# 3P4W_v1p0.net
KiCad netlist of a schematic drawn in EAGLE
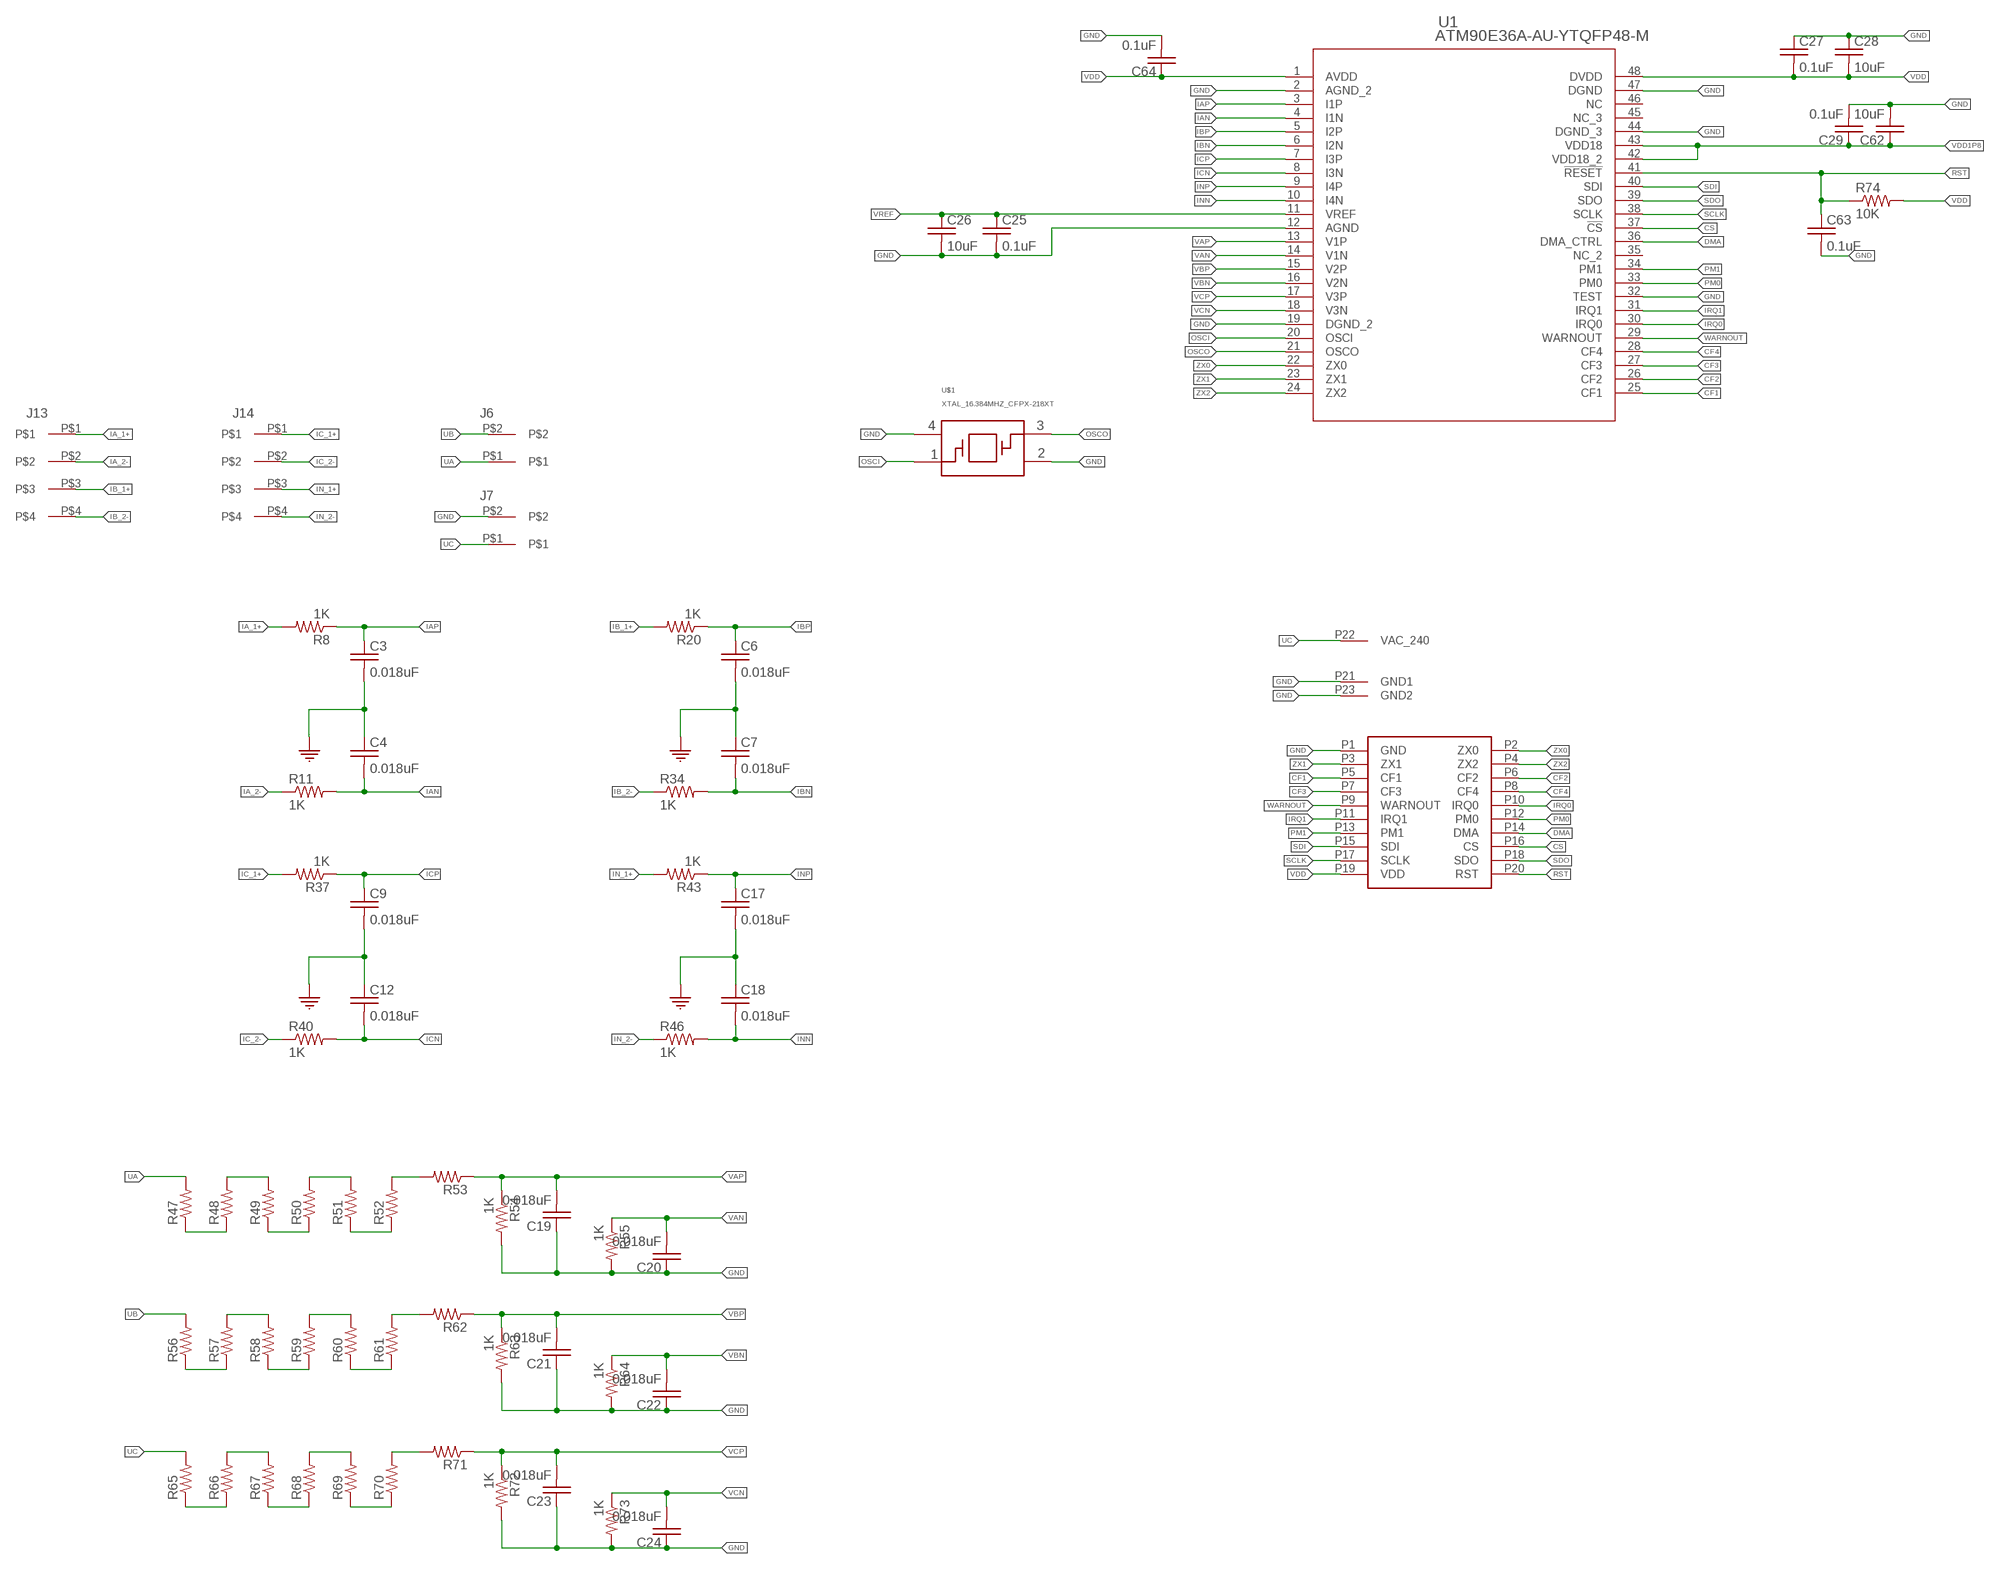
[diagram p0: schematic, sheet 1]

(export (version "E")
  (design (tool "Eeschema 10.0.6"))
  (components
    (comp (ref "C3")
      (value "0.018uF")
      (footprint "eagle-import:0402")
      (libsource (lib "eagle-import") (part "C_0402"))
    )
    (comp (ref "C4")
      (value "0.018uF")
      (footprint "eagle-import:0402")
      (libsource (lib "eagle-import") (part "C_0402"))
    )
    (comp (ref "C6")
      (value "0.018uF")
      (footprint "eagle-import:0402")
      (libsource (lib "eagle-import") (part "C_0402"))
    )
    (comp (ref "C7")
      (value "0.018uF")
      (footprint "eagle-import:0402")
      (libsource (lib "eagle-import") (part "C_0402"))
    )
    (comp (ref "C9")
      (value "0.018uF")
      (footprint "eagle-import:0402")
      (libsource (lib "eagle-import") (part "C_0402"))
    )
    (comp (ref "C12")
      (value "0.018uF")
      (footprint "eagle-import:0402")
      (libsource (lib "eagle-import") (part "C_0402"))
    )
    (comp (ref "C17")
      (value "0.018uF")
      (footprint "eagle-import:0402")
      (libsource (lib "eagle-import") (part "C_0402"))
    )
    (comp (ref "C18")
      (value "0.018uF")
      (footprint "eagle-import:0402")
      (libsource (lib "eagle-import") (part "C_0402"))
    )
    (comp (ref "C19")
      (value "0.018uF")
      (footprint "eagle-import:0402")
      (libsource (lib "eagle-import") (part "C_0402"))
    )
    (comp (ref "C20")
      (value "0.018uF")
      (footprint "eagle-import:0402")
      (libsource (lib "eagle-import") (part "C_0402"))
    )
    (comp (ref "C21")
      (value "0.018uF")
      (footprint "eagle-import:0402")
      (libsource (lib "eagle-import") (part "C_0402"))
    )
    (comp (ref "C22")
      (value "0.018uF")
      (footprint "eagle-import:0402")
      (libsource (lib "eagle-import") (part "C_0402"))
    )
    (comp (ref "C23")
      (value "0.018uF")
      (footprint "eagle-import:0402")
      (libsource (lib "eagle-import") (part "C_0402"))
    )
    (comp (ref "C24")
      (value "0.018uF")
      (footprint "eagle-import:0402")
      (libsource (lib "eagle-import") (part "C_0402"))
    )
    (comp (ref "C25")
      (value "0.1uF")
      (footprint "eagle-import:0402")
      (libsource (lib "eagle-import") (part "C_0402"))
    )
    (comp (ref "C26")
      (value "10uF")
      (footprint "eagle-import:0402")
      (libsource (lib "eagle-import") (part "C_0402"))
    )
    (comp (ref "C27")
      (value "0.1uF")
      (footprint "eagle-import:0402")
      (libsource (lib "eagle-import") (part "C_0402"))
    )
    (comp (ref "C28")
      (value "10uF")
      (footprint "eagle-import:0402")
      (libsource (lib "eagle-import") (part "C_0402"))
    )
    (comp (ref "C29")
      (value "0.1uF")
      (footprint "eagle-import:0402")
      (libsource (lib "eagle-import") (part "C_0402"))
    )
    (comp (ref "C62")
      (value "10uF")
      (footprint "eagle-import:0402")
      (libsource (lib "eagle-import") (part "C_0402"))
    )
    (comp (ref "C63")
      (value "0.1uF")
      (footprint "eagle-import:0402")
      (libsource (lib "eagle-import") (part "C_0402"))
    )
    (comp (ref "C64")
      (value "0.1uF")
      (footprint "eagle-import:0402")
      (libsource (lib "eagle-import") (part "C_0402"))
    )
    (comp (ref "J6")
      (value "3.81MM_1_X_2_RT_ANGLE_PLUG_HEADER")
      (footprint "eagle-import:2_3.81MM_PITCH")
      (libsource (lib "eagle-import") (part "3.81MM_1_X_2_RT_ANGLE_PLUG_HEADER"))
    )
    (comp (ref "J7")
      (value "3.81MM_1_X_2_RT_ANGLE_PLUG_HEADER")
      (footprint "eagle-import:2_3.81MM_PITCH")
      (libsource (lib "eagle-import") (part "3.81MM_1_X_2_RT_ANGLE_PLUG_HEADER"))
    )
    (comp (ref "J13")
      (value "3.81MM_1_X_4_RT_ANGLE_PLUG_HEADER")
      (footprint "eagle-import:1X4_3.81MM_PITCH")
      (libsource (lib "eagle-import") (part "3.81MM_1_X_4_RT_ANGLE_PLUG_HEADER"))
    )
    (comp (ref "J14")
      (value "3.81MM_1_X_4_RT_ANGLE_PLUG_HEADER")
      (footprint "eagle-import:1X4_3.81MM_PITCH")
      (libsource (lib "eagle-import") (part "3.81MM_1_X_4_RT_ANGLE_PLUG_HEADER"))
    )
    (comp (ref "R8")
      (value "1K")
      (footprint "eagle-import:0402")
      (libsource (lib "eagle-import") (part "R_0402"))
    )
    (comp (ref "R11")
      (value "1K")
      (footprint "eagle-import:0402")
      (libsource (lib "eagle-import") (part "R_0402"))
    )
    (comp (ref "R20")
      (value "1K")
      (footprint "eagle-import:0402")
      (libsource (lib "eagle-import") (part "R_0402"))
    )
    (comp (ref "R34")
      (value "1K")
      (footprint "eagle-import:0402")
      (libsource (lib "eagle-import") (part "R_0402"))
    )
    (comp (ref "R37")
      (value "1K")
      (footprint "eagle-import:0402")
      (libsource (lib "eagle-import") (part "R_0402"))
    )
    (comp (ref "R40")
      (value "1K")
      (footprint "eagle-import:0402")
      (libsource (lib "eagle-import") (part "R_0402"))
    )
    (comp (ref "R43")
      (value "1K")
      (footprint "eagle-import:0402")
      (libsource (lib "eagle-import") (part "R_0402"))
    )
    (comp (ref "R46")
      (value "1K")
      (footprint "eagle-import:0402")
      (libsource (lib "eagle-import") (part "R_0402"))
    )
    (comp (ref "R47")
      (value "R_0402")
      (footprint "eagle-import:0402")
      (libsource (lib "eagle-import") (part "R_0402"))
    )
    (comp (ref "R48")
      (value "R_0402")
      (footprint "eagle-import:0402")
      (libsource (lib "eagle-import") (part "R_0402"))
    )
    (comp (ref "R49")
      (value "R_0402")
      (footprint "eagle-import:0402")
      (libsource (lib "eagle-import") (part "R_0402"))
    )
    (comp (ref "R50")
      (value "R_0402")
      (footprint "eagle-import:0402")
      (libsource (lib "eagle-import") (part "R_0402"))
    )
    (comp (ref "R51")
      (value "R_0402")
      (footprint "eagle-import:0402")
      (libsource (lib "eagle-import") (part "R_0402"))
    )
    (comp (ref "R52")
      (value "R_0402")
      (footprint "eagle-import:0402")
      (libsource (lib "eagle-import") (part "R_0402"))
    )
    (comp (ref "R53")
      (value "R_0402")
      (footprint "eagle-import:0402")
      (libsource (lib "eagle-import") (part "R_0402"))
    )
    (comp (ref "R54")
      (value "1K")
      (footprint "eagle-import:0402")
      (libsource (lib "eagle-import") (part "R_0402"))
    )
    (comp (ref "R55")
      (value "1K")
      (footprint "eagle-import:0402")
      (libsource (lib "eagle-import") (part "R_0402"))
    )
    (comp (ref "R56")
      (value "R_0402")
      (footprint "eagle-import:0402")
      (libsource (lib "eagle-import") (part "R_0402"))
    )
    (comp (ref "R57")
      (value "R_0402")
      (footprint "eagle-import:0402")
      (libsource (lib "eagle-import") (part "R_0402"))
    )
    (comp (ref "R58")
      (value "R_0402")
      (footprint "eagle-import:0402")
      (libsource (lib "eagle-import") (part "R_0402"))
    )
    (comp (ref "R59")
      (value "R_0402")
      (footprint "eagle-import:0402")
      (libsource (lib "eagle-import") (part "R_0402"))
    )
    (comp (ref "R60")
      (value "R_0402")
      (footprint "eagle-import:0402")
      (libsource (lib "eagle-import") (part "R_0402"))
    )
    (comp (ref "R61")
      (value "R_0402")
      (footprint "eagle-import:0402")
      (libsource (lib "eagle-import") (part "R_0402"))
    )
    (comp (ref "R62")
      (value "R_0402")
      (footprint "eagle-import:0402")
      (libsource (lib "eagle-import") (part "R_0402"))
    )
    (comp (ref "R63")
      (value "1K")
      (footprint "eagle-import:0402")
      (libsource (lib "eagle-import") (part "R_0402"))
    )
    (comp (ref "R64")
      (value "1K")
      (footprint "eagle-import:0402")
      (libsource (lib "eagle-import") (part "R_0402"))
    )
    (comp (ref "R65")
      (value "R_0402")
      (footprint "eagle-import:0402")
      (libsource (lib "eagle-import") (part "R_0402"))
    )
    (comp (ref "R66")
      (value "R_0402")
      (footprint "eagle-import:0402")
      (libsource (lib "eagle-import") (part "R_0402"))
    )
    (comp (ref "R67")
      (value "R_0402")
      (footprint "eagle-import:0402")
      (libsource (lib "eagle-import") (part "R_0402"))
    )
    (comp (ref "R68")
      (value "R_0402")
      (footprint "eagle-import:0402")
      (libsource (lib "eagle-import") (part "R_0402"))
    )
    (comp (ref "R69")
      (value "R_0402")
      (footprint "eagle-import:0402")
      (libsource (lib "eagle-import") (part "R_0402"))
    )
    (comp (ref "R70")
      (value "R_0402")
      (footprint "eagle-import:0402")
      (libsource (lib "eagle-import") (part "R_0402"))
    )
    (comp (ref "R71")
      (value "R_0402")
      (footprint "eagle-import:0402")
      (libsource (lib "eagle-import") (part "R_0402"))
    )
    (comp (ref "R72")
      (value "1K")
      (footprint "eagle-import:0402")
      (libsource (lib "eagle-import") (part "R_0402"))
    )
    (comp (ref "R73")
      (value "1K")
      (footprint "eagle-import:0402")
      (libsource (lib "eagle-import") (part "R_0402"))
    )
    (comp (ref "R74")
      (value "10K")
      (footprint "eagle-import:0402")
      (libsource (lib "eagle-import") (part "R_0402"))
    )
    (comp (ref "U$1")
      (value "XTAL_16.384MHZ_CFPX-218XT")
      (footprint "eagle-import:XTAL_2.5X2.0")
      (libsource (lib "eagle-import") (part "XTAL_16.384MHZ_CFPX-218XT"))
    )
    (comp (ref "U$2")
      (value "METER_BASE")
      (footprint "eagle-import:METER_BASE")
      (libsource (lib "eagle-import") (part "METER_BASE"))
    )
    (comp (ref "U1")
      (value "ATM90E36A-AU-YTQFP48-M")
      (footprint "eagle-import:TQFP48-M")
      (fields (field (name "MANUFACTURER_PART_NUMBER") "ATM90E36AAUY"))
      (libsource (lib "eagle-import") (part "ATM90E36A-AU-YTQFP48-M"))
    )
  )
  (nets
    (net (code "1") (name "CF1") (class "Default")
      (node (ref "U$2") (pin "P5") (pinfunction "CF1_P5") (pintype "bidirectional"))
      (node (ref "U1") (pin "25") (pinfunction "CF1_25") (pintype "output"))
    )
    (net (code "2") (name "CF2") (class "Default")
      (node (ref "U$2") (pin "P6") (pinfunction "CF2_P6") (pintype "bidirectional"))
      (node (ref "U1") (pin "26") (pinfunction "CF2_26") (pintype "output"))
    )
    (net (code "3") (name "CF3") (class "Default")
      (node (ref "U$2") (pin "P7") (pinfunction "CF3_P7") (pintype "bidirectional"))
      (node (ref "U1") (pin "27") (pinfunction "CF3_27") (pintype "output"))
    )
    (net (code "4") (name "CF4") (class "Default")
      (node (ref "U$2") (pin "P8") (pinfunction "CF4_P8") (pintype "bidirectional"))
      (node (ref "U1") (pin "28") (pinfunction "CF4_28") (pintype "output"))
    )
    (net (code "5") (name "CS") (class "Default")
      (node (ref "U$2") (pin "P16") (pinfunction "CS_P16") (pintype "bidirectional"))
      (node (ref "U1") (pin "37") (pinfunction "~{CS}_37") (pintype "bidirectional"))
    )
    (net (code "6") (name "DMA") (class "Default")
      (node (ref "U$2") (pin "P14") (pinfunction "DMA_P14") (pintype "bidirectional"))
      (node (ref "U1") (pin "36") (pinfunction "DMA_CTRL_36") (pintype "input"))
    )
    (net (code "7") (name "GND") (class "Default")
      (node (ref "C12") (pin "P$1") (pinfunction "1_P$1") (pintype "passive"))
      (node (ref "C17") (pin "P$2") (pinfunction "2_P$2") (pintype "passive"))
      (node (ref "C18") (pin "P$1") (pinfunction "1_P$1") (pintype "passive"))
      (node (ref "C19") (pin "P$1") (pinfunction "1_P$1") (pintype "passive"))
      (node (ref "C20") (pin "P$1") (pinfunction "1_P$1") (pintype "passive"))
      (node (ref "C21") (pin "P$1") (pinfunction "1_P$1") (pintype "passive"))
      (node (ref "C22") (pin "P$1") (pinfunction "1_P$1") (pintype "passive"))
      (node (ref "C23") (pin "P$1") (pinfunction "1_P$1") (pintype "passive"))
      (node (ref "C24") (pin "P$1") (pinfunction "1_P$1") (pintype "passive"))
      (node (ref "C25") (pin "P$2") (pinfunction "2_P$2") (pintype "passive"))
      (node (ref "C26") (pin "P$2") (pinfunction "2_P$2") (pintype "passive"))
      (node (ref "C27") (pin "P$1") (pinfunction "1_P$1") (pintype "passive"))
      (node (ref "C28") (pin "P$1") (pinfunction "1_P$1") (pintype "passive"))
      (node (ref "C29") (pin "P$2") (pinfunction "2_P$2") (pintype "passive"))
      (node (ref "C3") (pin "P$2") (pinfunction "2_P$2") (pintype "passive"))
      (node (ref "C4") (pin "P$1") (pinfunction "1_P$1") (pintype "passive"))
      (node (ref "C6") (pin "P$2") (pinfunction "2_P$2") (pintype "passive"))
      (node (ref "C62") (pin "P$2") (pinfunction "2_P$2") (pintype "passive"))
      (node (ref "C63") (pin "P$2") (pinfunction "2_P$2") (pintype "passive"))
      (node (ref "C64") (pin "P$2") (pinfunction "2_P$2") (pintype "passive"))
      (node (ref "C7") (pin "P$1") (pinfunction "1_P$1") (pintype "passive"))
      (node (ref "C9") (pin "P$2") (pinfunction "2_P$2") (pintype "passive"))
      (node (ref "J7") (pin "P$2") (pinfunction "P$2_P$2") (pintype "bidirectional"))
      (node (ref "R54") (pin "P$2") (pinfunction "2_P$2") (pintype "passive"))
      (node (ref "R55") (pin "P$2") (pinfunction "2_P$2") (pintype "passive"))
      (node (ref "R63") (pin "P$2") (pinfunction "2_P$2") (pintype "passive"))
      (node (ref "R64") (pin "P$2") (pinfunction "2_P$2") (pintype "passive"))
      (node (ref "R72") (pin "P$2") (pinfunction "2_P$2") (pintype "passive"))
      (node (ref "R73") (pin "P$2") (pinfunction "2_P$2") (pintype "passive"))
      (node (ref "U$1") (pin "2") (pinfunction "2_2") (pintype "bidirectional"))
      (node (ref "U$1") (pin "4") (pinfunction "4_4") (pintype "bidirectional"))
      (node (ref "U$2") (pin "P1") (pinfunction "GND_P1") (pintype "bidirectional"))
      (node (ref "U$2") (pin "P21") (pinfunction "GND1_P21") (pintype "bidirectional"))
      (node (ref "U$2") (pin "P23") (pinfunction "GND2_P23") (pintype "bidirectional"))
      (node (ref "U1") (pin "12") (pinfunction "AGND_12") (pintype "power_in"))
      (node (ref "U1") (pin "19") (pinfunction "DGND_2_19") (pintype "power_in"))
      (node (ref "U1") (pin "2") (pinfunction "AGND_2_2") (pintype "power_in"))
      (node (ref "U1") (pin "32") (pinfunction "TEST_32") (pintype "input"))
      (node (ref "U1") (pin "44") (pinfunction "DGND_3_44") (pintype "power_in"))
      (node (ref "U1") (pin "47") (pinfunction "DGND_47") (pintype "power_in"))
    )
    (net (code "8") (name "IAN") (class "Default")
      (node (ref "C4") (pin "P$2") (pinfunction "2_P$2") (pintype "passive"))
      (node (ref "R11") (pin "P$2") (pinfunction "2_P$2") (pintype "passive"))
      (node (ref "U1") (pin "4") (pinfunction "I1N_4") (pintype "input"))
    )
    (net (code "9") (name "IAP") (class "Default")
      (node (ref "C3") (pin "P$1") (pinfunction "1_P$1") (pintype "passive"))
      (node (ref "R8") (pin "P$1") (pinfunction "1_P$1") (pintype "passive"))
      (node (ref "U1") (pin "3") (pinfunction "I1P_3") (pintype "input"))
    )
    (net (code "10") (name "IA_1+") (class "Default")
      (node (ref "J13") (pin "P$1") (pinfunction "P$1_P$1") (pintype "bidirectional"))
      (node (ref "R8") (pin "P$2") (pinfunction "2_P$2") (pintype "passive"))
    )
    (net (code "11") (name "IA_2-") (class "Default")
      (node (ref "J13") (pin "P$2") (pinfunction "P$2_P$2") (pintype "bidirectional"))
      (node (ref "R11") (pin "P$1") (pinfunction "1_P$1") (pintype "passive"))
    )
    (net (code "12") (name "IBN") (class "Default")
      (node (ref "C7") (pin "P$2") (pinfunction "2_P$2") (pintype "passive"))
      (node (ref "R34") (pin "P$2") (pinfunction "2_P$2") (pintype "passive"))
      (node (ref "U1") (pin "6") (pinfunction "I2N_6") (pintype "input"))
    )
    (net (code "13") (name "IBP") (class "Default")
      (node (ref "C6") (pin "P$1") (pinfunction "1_P$1") (pintype "passive"))
      (node (ref "R20") (pin "P$1") (pinfunction "1_P$1") (pintype "passive"))
      (node (ref "U1") (pin "5") (pinfunction "I2P_5") (pintype "input"))
    )
    (net (code "14") (name "IB_1+") (class "Default")
      (node (ref "J13") (pin "P$3") (pinfunction "P$3_P$3") (pintype "bidirectional"))
      (node (ref "R20") (pin "P$2") (pinfunction "2_P$2") (pintype "passive"))
    )
    (net (code "15") (name "IB_2-") (class "Default")
      (node (ref "J13") (pin "P$4") (pinfunction "P$4_P$4") (pintype "bidirectional"))
      (node (ref "R34") (pin "P$1") (pinfunction "1_P$1") (pintype "passive"))
    )
    (net (code "16") (name "ICN") (class "Default")
      (node (ref "C12") (pin "P$2") (pinfunction "2_P$2") (pintype "passive"))
      (node (ref "R40") (pin "P$2") (pinfunction "2_P$2") (pintype "passive"))
      (node (ref "U1") (pin "8") (pinfunction "I3N_8") (pintype "input"))
    )
    (net (code "17") (name "ICP") (class "Default")
      (node (ref "C9") (pin "P$1") (pinfunction "1_P$1") (pintype "passive"))
      (node (ref "R37") (pin "P$1") (pinfunction "1_P$1") (pintype "passive"))
      (node (ref "U1") (pin "7") (pinfunction "I3P_7") (pintype "input"))
    )
    (net (code "18") (name "IC_1+") (class "Default")
      (node (ref "J14") (pin "P$1") (pinfunction "P$1_P$1") (pintype "bidirectional"))
      (node (ref "R37") (pin "P$2") (pinfunction "2_P$2") (pintype "passive"))
    )
    (net (code "19") (name "IC_2-") (class "Default")
      (node (ref "J14") (pin "P$2") (pinfunction "P$2_P$2") (pintype "bidirectional"))
      (node (ref "R40") (pin "P$1") (pinfunction "1_P$1") (pintype "passive"))
    )
    (net (code "20") (name "INN") (class "Default")
      (node (ref "C18") (pin "P$2") (pinfunction "2_P$2") (pintype "passive"))
      (node (ref "R46") (pin "P$2") (pinfunction "2_P$2") (pintype "passive"))
      (node (ref "U1") (pin "10") (pinfunction "I4N_10") (pintype "input"))
    )
    (net (code "21") (name "INP") (class "Default")
      (node (ref "C17") (pin "P$1") (pinfunction "1_P$1") (pintype "passive"))
      (node (ref "R43") (pin "P$1") (pinfunction "1_P$1") (pintype "passive"))
      (node (ref "U1") (pin "9") (pinfunction "I4P_9") (pintype "input"))
    )
    (net (code "22") (name "IN_1+") (class "Default")
      (node (ref "J14") (pin "P$3") (pinfunction "P$3_P$3") (pintype "bidirectional"))
      (node (ref "R43") (pin "P$2") (pinfunction "2_P$2") (pintype "passive"))
    )
    (net (code "23") (name "IN_2-") (class "Default")
      (node (ref "J14") (pin "P$4") (pinfunction "P$4_P$4") (pintype "bidirectional"))
      (node (ref "R46") (pin "P$1") (pinfunction "1_P$1") (pintype "passive"))
    )
    (net (code "24") (name "IRQ0") (class "Default")
      (node (ref "U$2") (pin "P10") (pinfunction "IRQ0_P10") (pintype "bidirectional"))
      (node (ref "U1") (pin "30") (pinfunction "IRQ0_30") (pintype "output"))
    )
    (net (code "25") (name "IRQ1") (class "Default")
      (node (ref "U$2") (pin "P11") (pinfunction "IRQ1_P11") (pintype "bidirectional"))
      (node (ref "U1") (pin "31") (pinfunction "IRQ1_31") (pintype "output"))
    )
    (net (code "26") (name "Net-(R47-1)") (class "Default")
      (node (ref "R47") (pin "P$1") (pinfunction "1_P$1") (pintype "passive"))
      (node (ref "R48") (pin "P$1") (pinfunction "1_P$1") (pintype "passive"))
    )
    (net (code "27") (name "Net-(R48-2)") (class "Default")
      (node (ref "R48") (pin "P$2") (pinfunction "2_P$2") (pintype "passive"))
      (node (ref "R49") (pin "P$2") (pinfunction "2_P$2") (pintype "passive"))
    )
    (net (code "28") (name "Net-(R49-1)") (class "Default")
      (node (ref "R49") (pin "P$1") (pinfunction "1_P$1") (pintype "passive"))
      (node (ref "R50") (pin "P$1") (pinfunction "1_P$1") (pintype "passive"))
    )
    (net (code "29") (name "Net-(R50-2)") (class "Default")
      (node (ref "R50") (pin "P$2") (pinfunction "2_P$2") (pintype "passive"))
      (node (ref "R51") (pin "P$2") (pinfunction "2_P$2") (pintype "passive"))
    )
    (net (code "30") (name "Net-(R51-1)") (class "Default")
      (node (ref "R51") (pin "P$1") (pinfunction "1_P$1") (pintype "passive"))
      (node (ref "R52") (pin "P$1") (pinfunction "1_P$1") (pintype "passive"))
    )
    (net (code "31") (name "Net-(R52-2)") (class "Default")
      (node (ref "R52") (pin "P$2") (pinfunction "2_P$2") (pintype "passive"))
      (node (ref "R53") (pin "P$2") (pinfunction "2_P$2") (pintype "passive"))
    )
    (net (code "32") (name "Net-(R56-1)") (class "Default")
      (node (ref "R56") (pin "P$1") (pinfunction "1_P$1") (pintype "passive"))
      (node (ref "R57") (pin "P$1") (pinfunction "1_P$1") (pintype "passive"))
    )
    (net (code "33") (name "Net-(R57-2)") (class "Default")
      (node (ref "R57") (pin "P$2") (pinfunction "2_P$2") (pintype "passive"))
      (node (ref "R58") (pin "P$2") (pinfunction "2_P$2") (pintype "passive"))
    )
    (net (code "34") (name "Net-(R58-1)") (class "Default")
      (node (ref "R58") (pin "P$1") (pinfunction "1_P$1") (pintype "passive"))
      (node (ref "R59") (pin "P$1") (pinfunction "1_P$1") (pintype "passive"))
    )
    (net (code "35") (name "Net-(R59-2)") (class "Default")
      (node (ref "R59") (pin "P$2") (pinfunction "2_P$2") (pintype "passive"))
      (node (ref "R60") (pin "P$2") (pinfunction "2_P$2") (pintype "passive"))
    )
    (net (code "36") (name "Net-(R60-1)") (class "Default")
      (node (ref "R60") (pin "P$1") (pinfunction "1_P$1") (pintype "passive"))
      (node (ref "R61") (pin "P$1") (pinfunction "1_P$1") (pintype "passive"))
    )
    (net (code "37") (name "Net-(R61-2)") (class "Default")
      (node (ref "R61") (pin "P$2") (pinfunction "2_P$2") (pintype "passive"))
      (node (ref "R62") (pin "P$2") (pinfunction "2_P$2") (pintype "passive"))
    )
    (net (code "38") (name "Net-(R65-1)") (class "Default")
      (node (ref "R65") (pin "P$1") (pinfunction "1_P$1") (pintype "passive"))
      (node (ref "R66") (pin "P$1") (pinfunction "1_P$1") (pintype "passive"))
    )
    (net (code "39") (name "Net-(R66-2)") (class "Default")
      (node (ref "R66") (pin "P$2") (pinfunction "2_P$2") (pintype "passive"))
      (node (ref "R67") (pin "P$2") (pinfunction "2_P$2") (pintype "passive"))
    )
    (net (code "40") (name "Net-(R67-1)") (class "Default")
      (node (ref "R67") (pin "P$1") (pinfunction "1_P$1") (pintype "passive"))
      (node (ref "R68") (pin "P$1") (pinfunction "1_P$1") (pintype "passive"))
    )
    (net (code "41") (name "Net-(R68-2)") (class "Default")
      (node (ref "R68") (pin "P$2") (pinfunction "2_P$2") (pintype "passive"))
      (node (ref "R69") (pin "P$2") (pinfunction "2_P$2") (pintype "passive"))
    )
    (net (code "42") (name "Net-(R69-1)") (class "Default")
      (node (ref "R69") (pin "P$1") (pinfunction "1_P$1") (pintype "passive"))
      (node (ref "R70") (pin "P$1") (pinfunction "1_P$1") (pintype "passive"))
    )
    (net (code "43") (name "Net-(R70-2)") (class "Default")
      (node (ref "R70") (pin "P$2") (pinfunction "2_P$2") (pintype "passive"))
      (node (ref "R71") (pin "P$2") (pinfunction "2_P$2") (pintype "passive"))
    )
    (net (code "44") (name "OSCI") (class "Default")
      (node (ref "U$1") (pin "1") (pinfunction "1_1") (pintype "bidirectional"))
      (node (ref "U1") (pin "20") (pinfunction "OSCI_20") (pintype "input"))
    )
    (net (code "45") (name "OSCO") (class "Default")
      (node (ref "U$1") (pin "3") (pinfunction "3_3") (pintype "bidirectional"))
      (node (ref "U1") (pin "21") (pinfunction "OSCO_21") (pintype "output"))
    )
    (net (code "46") (name "PM0") (class "Default")
      (node (ref "U$2") (pin "P12") (pinfunction "PM0_P12") (pintype "bidirectional"))
      (node (ref "U1") (pin "33") (pinfunction "PM0_33") (pintype "input"))
    )
    (net (code "47") (name "PM1") (class "Default")
      (node (ref "U$2") (pin "P13") (pinfunction "PM1_P13") (pintype "bidirectional"))
      (node (ref "U1") (pin "34") (pinfunction "PM1_34") (pintype "input"))
    )
    (net (code "48") (name "RST") (class "Default")
      (node (ref "C63") (pin "P$1") (pinfunction "1_P$1") (pintype "passive"))
      (node (ref "R74") (pin "P$1") (pinfunction "1_P$1") (pintype "passive"))
      (node (ref "U$2") (pin "P20") (pinfunction "RST_P20") (pintype "bidirectional"))
      (node (ref "U1") (pin "41") (pinfunction "~{RESET}_41") (pintype "input"))
    )
    (net (code "49") (name "SCLK") (class "Default")
      (node (ref "U$2") (pin "P17") (pinfunction "SCLK_P17") (pintype "bidirectional"))
      (node (ref "U1") (pin "38") (pinfunction "SCLK_38") (pintype "bidirectional"))
    )
    (net (code "50") (name "SDI") (class "Default")
      (node (ref "U$2") (pin "P15") (pinfunction "SDI_P15") (pintype "bidirectional"))
      (node (ref "U1") (pin "40") (pinfunction "SDI_40") (pintype "bidirectional"))
    )
    (net (code "51") (name "SDO") (class "Default")
      (node (ref "U$2") (pin "P18") (pinfunction "SDO_P18") (pintype "bidirectional"))
      (node (ref "U1") (pin "39") (pinfunction "SDO_39") (pintype "bidirectional"))
    )
    (net (code "52") (name "UA") (class "Default")
      (node (ref "J6") (pin "P$1") (pinfunction "P$1_P$1") (pintype "bidirectional"))
      (node (ref "R47") (pin "P$2") (pinfunction "2_P$2") (pintype "passive"))
    )
    (net (code "53") (name "UB") (class "Default")
      (node (ref "J6") (pin "P$2") (pinfunction "P$2_P$2") (pintype "bidirectional"))
      (node (ref "R56") (pin "P$2") (pinfunction "2_P$2") (pintype "passive"))
    )
    (net (code "54") (name "UC") (class "Default")
      (node (ref "J7") (pin "P$1") (pinfunction "P$1_P$1") (pintype "bidirectional"))
      (node (ref "R65") (pin "P$2") (pinfunction "2_P$2") (pintype "passive"))
      (node (ref "U$2") (pin "P22") (pinfunction "VAC_240_P22") (pintype "bidirectional"))
    )
    (net (code "55") (name "VAN") (class "Default")
      (node (ref "C20") (pin "P$2") (pinfunction "2_P$2") (pintype "passive"))
      (node (ref "R55") (pin "P$1") (pinfunction "1_P$1") (pintype "passive"))
      (node (ref "U1") (pin "14") (pinfunction "V1N_14") (pintype "input"))
    )
    (net (code "56") (name "VAP") (class "Default")
      (node (ref "C19") (pin "P$2") (pinfunction "2_P$2") (pintype "passive"))
      (node (ref "R53") (pin "P$1") (pinfunction "1_P$1") (pintype "passive"))
      (node (ref "R54") (pin "P$1") (pinfunction "1_P$1") (pintype "passive"))
      (node (ref "U1") (pin "13") (pinfunction "V1P_13") (pintype "input"))
    )
    (net (code "57") (name "VBN") (class "Default")
      (node (ref "C22") (pin "P$2") (pinfunction "2_P$2") (pintype "passive"))
      (node (ref "R64") (pin "P$1") (pinfunction "1_P$1") (pintype "passive"))
      (node (ref "U1") (pin "16") (pinfunction "V2N_16") (pintype "input"))
    )
    (net (code "58") (name "VBP") (class "Default")
      (node (ref "C21") (pin "P$2") (pinfunction "2_P$2") (pintype "passive"))
      (node (ref "R62") (pin "P$1") (pinfunction "1_P$1") (pintype "passive"))
      (node (ref "R63") (pin "P$1") (pinfunction "1_P$1") (pintype "passive"))
      (node (ref "U1") (pin "15") (pinfunction "V2P_15") (pintype "input"))
    )
    (net (code "59") (name "VCN") (class "Default")
      (node (ref "C24") (pin "P$2") (pinfunction "2_P$2") (pintype "passive"))
      (node (ref "R73") (pin "P$1") (pinfunction "1_P$1") (pintype "passive"))
      (node (ref "U1") (pin "18") (pinfunction "V3N_18") (pintype "input"))
    )
    (net (code "60") (name "VCP") (class "Default")
      (node (ref "C23") (pin "P$2") (pinfunction "2_P$2") (pintype "passive"))
      (node (ref "R71") (pin "P$1") (pinfunction "1_P$1") (pintype "passive"))
      (node (ref "R72") (pin "P$1") (pinfunction "1_P$1") (pintype "passive"))
      (node (ref "U1") (pin "17") (pinfunction "V3P_17") (pintype "input"))
    )
    (net (code "61") (name "VDD") (class "Default")
      (node (ref "C27") (pin "P$2") (pinfunction "2_P$2") (pintype "passive"))
      (node (ref "C28") (pin "P$2") (pinfunction "2_P$2") (pintype "passive"))
      (node (ref "C64") (pin "P$1") (pinfunction "1_P$1") (pintype "passive"))
      (node (ref "R74") (pin "P$2") (pinfunction "2_P$2") (pintype "passive"))
      (node (ref "U$2") (pin "P19") (pinfunction "VDD_P19") (pintype "bidirectional"))
      (node (ref "U1") (pin "1") (pinfunction "AVDD_1") (pintype "power_in"))
      (node (ref "U1") (pin "48") (pinfunction "DVDD_48") (pintype "power_in"))
    )
    (net (code "62") (name "VDD1P8") (class "Default")
      (node (ref "C29") (pin "P$1") (pinfunction "1_P$1") (pintype "passive"))
      (node (ref "C62") (pin "P$1") (pinfunction "1_P$1") (pintype "passive"))
      (node (ref "U1") (pin "42") (pinfunction "VDD18_2_42") (pintype "power_in"))
      (node (ref "U1") (pin "43") (pinfunction "VDD18_43") (pintype "power_in"))
    )
    (net (code "63") (name "VREF") (class "Default")
      (node (ref "C25") (pin "P$1") (pinfunction "1_P$1") (pintype "passive"))
      (node (ref "C26") (pin "P$1") (pinfunction "1_P$1") (pintype "passive"))
      (node (ref "U1") (pin "11") (pinfunction "VREF_11") (pintype "output"))
    )
    (net (code "64") (name "WARNOUT") (class "Default")
      (node (ref "U$2") (pin "P9") (pinfunction "WARNOUT_P9") (pintype "bidirectional"))
      (node (ref "U1") (pin "29") (pinfunction "WARNOUT_29") (pintype "output"))
    )
    (net (code "65") (name "ZX0") (class "Default")
      (node (ref "U$2") (pin "P2") (pinfunction "ZX0_P2") (pintype "bidirectional"))
      (node (ref "U1") (pin "22") (pinfunction "ZX0_22") (pintype "output"))
    )
    (net (code "66") (name "ZX1") (class "Default")
      (node (ref "U$2") (pin "P3") (pinfunction "ZX1_P3") (pintype "bidirectional"))
      (node (ref "U1") (pin "23") (pinfunction "ZX1_23") (pintype "output"))
    )
    (net (code "67") (name "ZX2") (class "Default")
      (node (ref "U$2") (pin "P4") (pinfunction "ZX2_P4") (pintype "bidirectional"))
      (node (ref "U1") (pin "24") (pinfunction "ZX2_24") (pintype "output"))
    )
    (net (code "68") (name "unconnected-(U1-NC-Pad46)") (class "Default")
      (node (ref "U1") (pin "46") (pinfunction "NC_46") (pintype "no_connect"))
    )
    (net (code "69") (name "unconnected-(U1-NC_2-Pad35)") (class "Default")
      (node (ref "U1") (pin "35") (pinfunction "NC_2_35") (pintype "no_connect"))
    )
    (net (code "70") (name "unconnected-(U1-NC_3-Pad45)") (class "Default")
      (node (ref "U1") (pin "45") (pinfunction "NC_3_45") (pintype "no_connect"))
    )
  )
)
